# FPGA_1_V1_01.net
KiCad netlist of a schematic drawn in Altium Designer
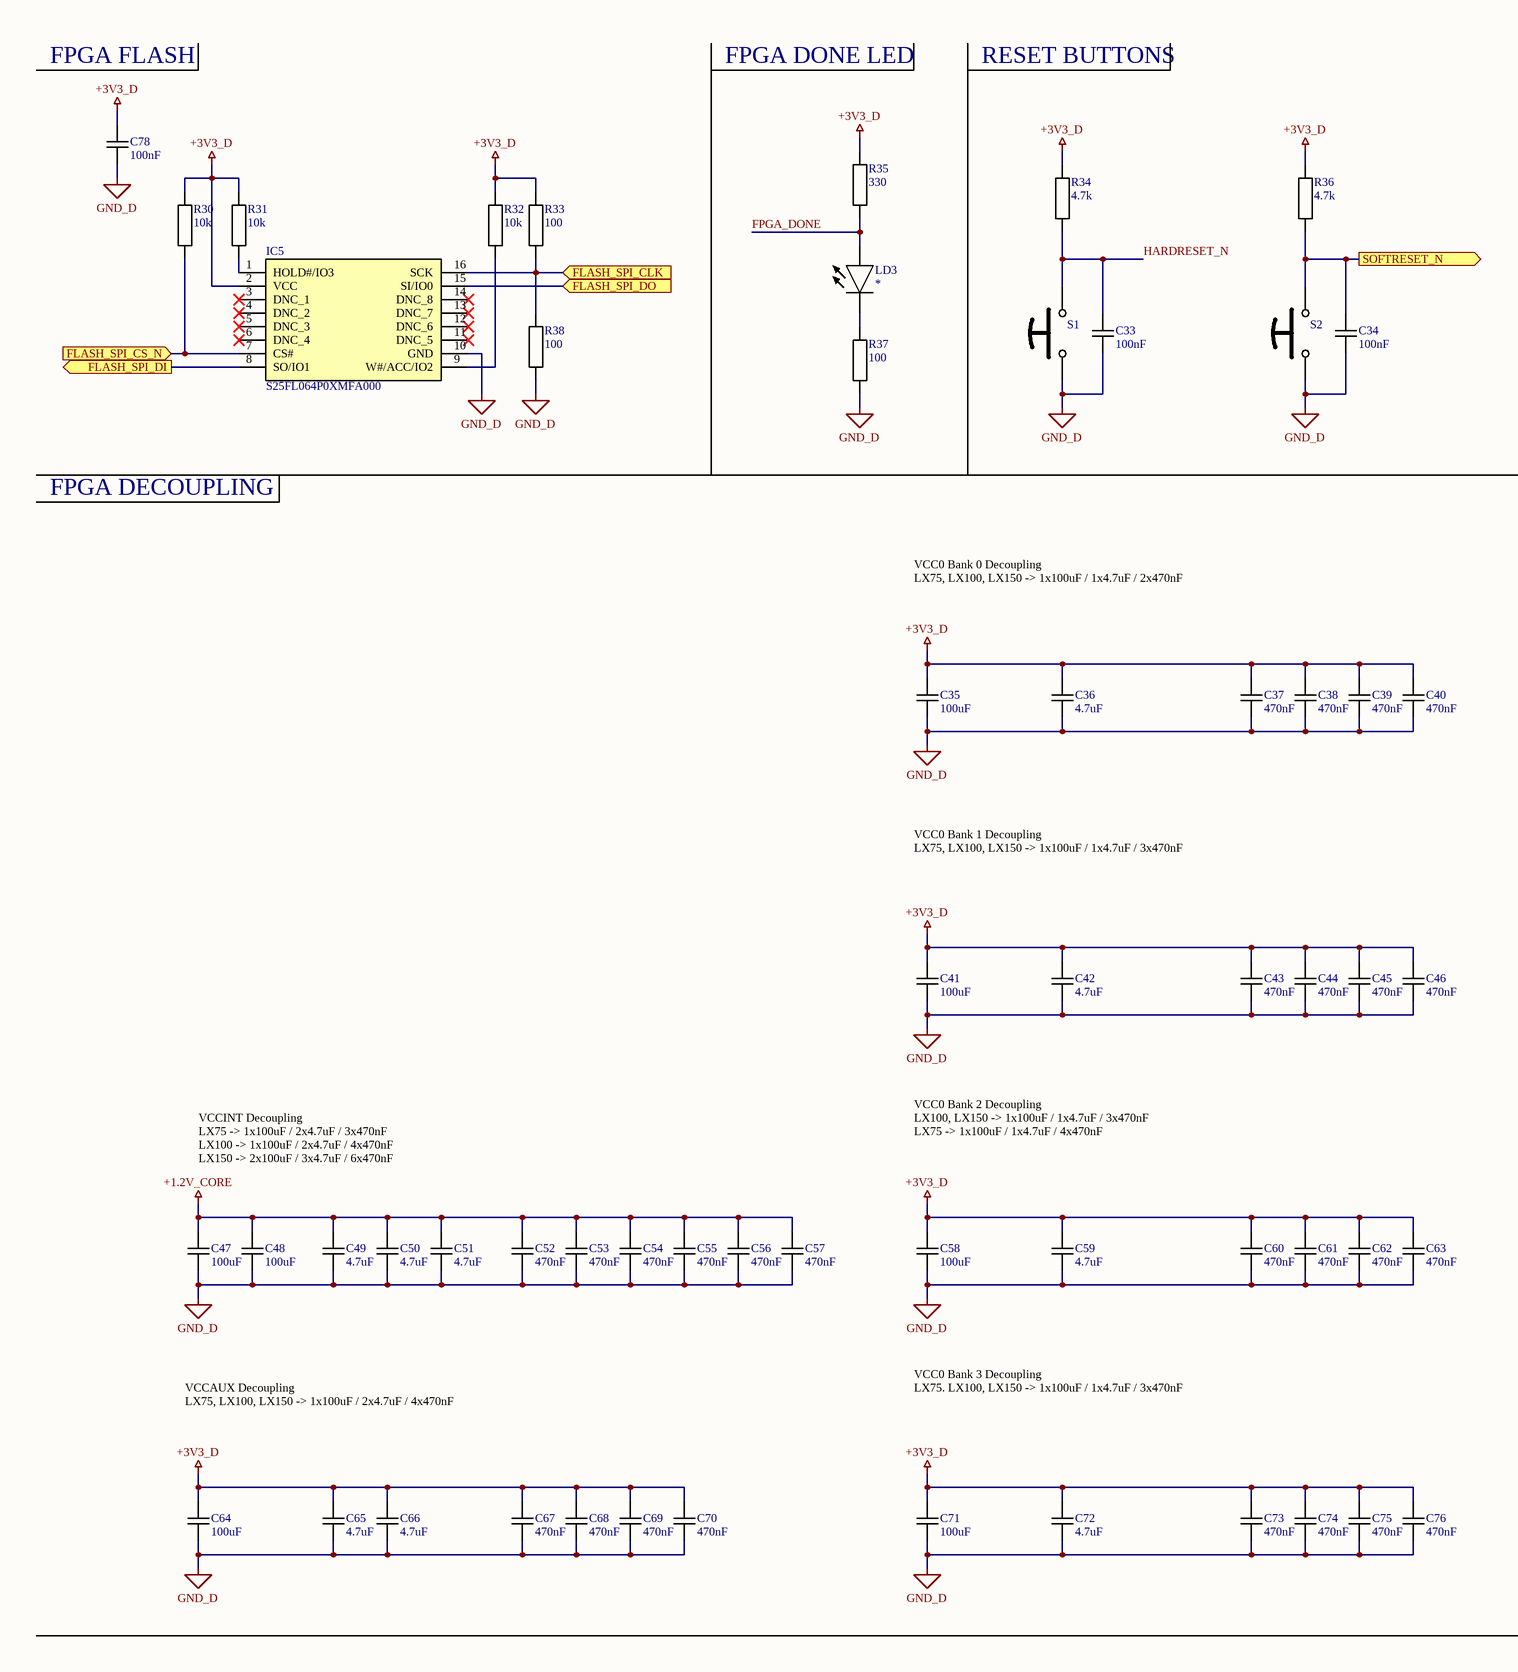
[diagram p0: FPGA_1_V1_01.SchDoc, left]
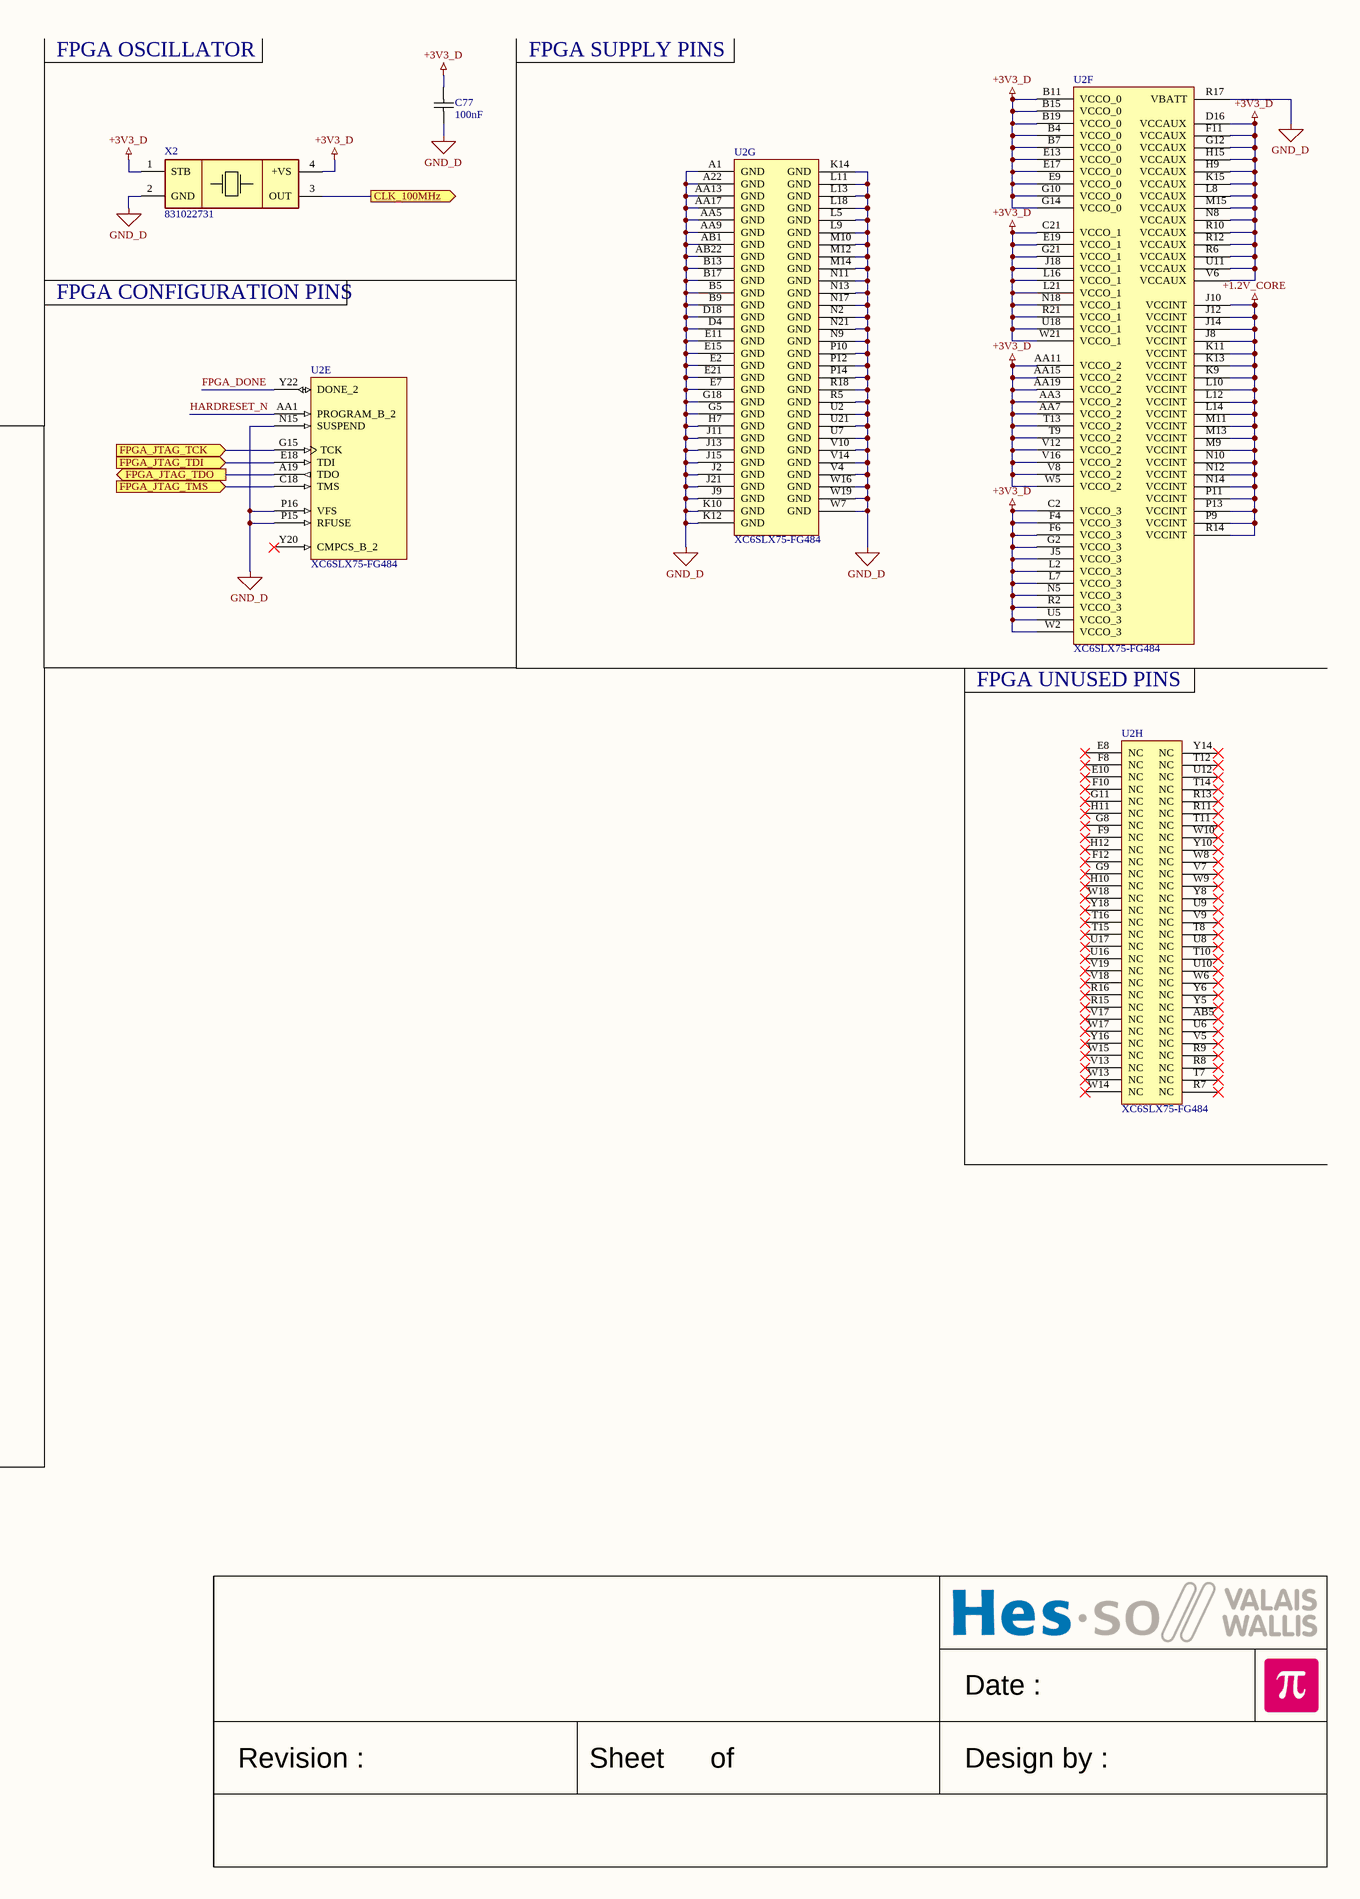
[diagram p1: FPGA_1_V1_01.SchDoc, right]

(export (version "E")
  (design (tool "Eeschema 10.0.6"))
  (components
    (comp (ref "C33")
      (value "100nF")
      (footprint "CAPACITOR 1608 REFLOW")
      (description "Capacitor")
      (libsource (lib "Capacitor") (part "Capacitor"))
    )
    (comp (ref "C34")
      (value "100nF")
      (footprint "CAPACITOR 1608 REFLOW")
      (description "Capacitor")
      (libsource (lib "Capacitor") (part "Capacitor"))
    )
    (comp (ref "C35")
      (value "100uF")
      (footprint "CAPACITOR 3216 REFLOW")
      (description "Capacitor")
      (libsource (lib "Capacitor") (part "Capacitor"))
    )
    (comp (ref "C36")
      (value "4.7uF")
      (footprint "CAPACITOR 1608 REFLOW")
      (description "Capacitor")
      (libsource (lib "Capacitor") (part "Capacitor"))
    )
    (comp (ref "C37")
      (value "470nF")
      (footprint "CAPACITOR 1005 REFLOW")
      (description "Capacitor")
      (libsource (lib "Capacitor") (part "Capacitor"))
    )
    (comp (ref "C38")
      (value "470nF")
      (footprint "CAPACITOR 1005 REFLOW")
      (description "Capacitor")
      (libsource (lib "Capacitor") (part "Capacitor"))
    )
    (comp (ref "C39")
      (value "470nF")
      (footprint "CAPACITOR 1005 REFLOW")
      (description "Capacitor")
      (libsource (lib "Capacitor") (part "Capacitor"))
    )
    (comp (ref "C40")
      (value "470nF")
      (footprint "CAPACITOR 1005 REFLOW")
      (description "Capacitor")
      (libsource (lib "Capacitor") (part "Capacitor"))
    )
    (comp (ref "C41")
      (value "100uF")
      (footprint "CAPACITOR 3216 REFLOW")
      (description "Capacitor")
      (libsource (lib "Capacitor") (part "Capacitor"))
    )
    (comp (ref "C42")
      (value "4.7uF")
      (footprint "CAPACITOR 1608 REFLOW")
      (description "Capacitor")
      (libsource (lib "Capacitor") (part "Capacitor"))
    )
    (comp (ref "C43")
      (value "470nF")
      (footprint "CAPACITOR 1005 REFLOW")
      (description "Capacitor")
      (libsource (lib "Capacitor") (part "Capacitor"))
    )
    (comp (ref "C44")
      (value "470nF")
      (footprint "CAPACITOR 1005 REFLOW")
      (description "Capacitor")
      (libsource (lib "Capacitor") (part "Capacitor"))
    )
    (comp (ref "C45")
      (value "470nF")
      (footprint "CAPACITOR 1005 REFLOW")
      (description "Capacitor")
      (libsource (lib "Capacitor") (part "Capacitor"))
    )
    (comp (ref "C46")
      (value "470nF")
      (footprint "CAPACITOR 1005 REFLOW")
      (description "Capacitor")
      (libsource (lib "Capacitor") (part "Capacitor"))
    )
    (comp (ref "C47")
      (value "100uF")
      (footprint "CAPACITOR 3216 REFLOW")
      (description "Capacitor")
      (libsource (lib "Capacitor") (part "Capacitor"))
    )
    (comp (ref "C48")
      (value "100uF")
      (footprint "CAPACITOR 3216 REFLOW")
      (description "Capacitor")
      (libsource (lib "Capacitor") (part "Capacitor"))
    )
    (comp (ref "C49")
      (value "4.7uF")
      (footprint "CAPACITOR 1608 REFLOW")
      (description "Capacitor")
      (libsource (lib "Capacitor") (part "Capacitor"))
    )
    (comp (ref "C50")
      (value "4.7uF")
      (footprint "CAPACITOR 1608 REFLOW")
      (description "Capacitor")
      (libsource (lib "Capacitor") (part "Capacitor"))
    )
    (comp (ref "C51")
      (value "4.7uF")
      (footprint "CAPACITOR 1608 REFLOW")
      (description "Capacitor")
      (libsource (lib "Capacitor") (part "Capacitor"))
    )
    (comp (ref "C52")
      (value "470nF")
      (footprint "CAPACITOR 1005 REFLOW")
      (description "Capacitor")
      (libsource (lib "Capacitor") (part "Capacitor"))
    )
    (comp (ref "C53")
      (value "470nF")
      (footprint "CAPACITOR 1005 REFLOW")
      (description "Capacitor")
      (libsource (lib "Capacitor") (part "Capacitor"))
    )
    (comp (ref "C54")
      (value "470nF")
      (footprint "CAPACITOR 1005 REFLOW")
      (description "Capacitor")
      (libsource (lib "Capacitor") (part "Capacitor"))
    )
    (comp (ref "C55")
      (value "470nF")
      (footprint "CAPACITOR 1005 REFLOW")
      (description "Capacitor")
      (libsource (lib "Capacitor") (part "Capacitor"))
    )
    (comp (ref "C56")
      (value "470nF")
      (footprint "CAPACITOR 1005 REFLOW")
      (description "Capacitor")
      (libsource (lib "Capacitor") (part "Capacitor"))
    )
    (comp (ref "C57")
      (value "470nF")
      (footprint "CAPACITOR 1005 REFLOW")
      (description "Capacitor")
      (libsource (lib "Capacitor") (part "Capacitor"))
    )
    (comp (ref "C58")
      (value "100uF")
      (footprint "CAPACITOR 3216 REFLOW")
      (description "Capacitor")
      (libsource (lib "Capacitor") (part "Capacitor"))
    )
    (comp (ref "C59")
      (value "4.7uF")
      (footprint "CAPACITOR 1608 REFLOW")
      (description "Capacitor")
      (libsource (lib "Capacitor") (part "Capacitor"))
    )
    (comp (ref "C60")
      (value "470nF")
      (footprint "CAPACITOR 1005 REFLOW")
      (description "Capacitor")
      (libsource (lib "Capacitor") (part "Capacitor"))
    )
    (comp (ref "C61")
      (value "470nF")
      (footprint "CAPACITOR 1005 REFLOW")
      (description "Capacitor")
      (libsource (lib "Capacitor") (part "Capacitor"))
    )
    (comp (ref "C62")
      (value "470nF")
      (footprint "CAPACITOR 1005 REFLOW")
      (description "Capacitor")
      (libsource (lib "Capacitor") (part "Capacitor"))
    )
    (comp (ref "C63")
      (value "470nF")
      (footprint "CAPACITOR 1005 REFLOW")
      (description "Capacitor")
      (libsource (lib "Capacitor") (part "Capacitor"))
    )
    (comp (ref "C64")
      (value "100uF")
      (footprint "CAPACITOR 3216 REFLOW")
      (description "Capacitor")
      (libsource (lib "Capacitor") (part "Capacitor"))
    )
    (comp (ref "C65")
      (value "4.7uF")
      (footprint "CAPACITOR 1608 REFLOW")
      (description "Capacitor")
      (libsource (lib "Capacitor") (part "Capacitor"))
    )
    (comp (ref "C66")
      (value "4.7uF")
      (footprint "CAPACITOR 1608 REFLOW")
      (description "Capacitor")
      (libsource (lib "Capacitor") (part "Capacitor"))
    )
    (comp (ref "C67")
      (value "470nF")
      (footprint "CAPACITOR 1005 REFLOW")
      (description "Capacitor")
      (libsource (lib "Capacitor") (part "Capacitor"))
    )
    (comp (ref "C68")
      (value "470nF")
      (footprint "CAPACITOR 1005 REFLOW")
      (description "Capacitor")
      (libsource (lib "Capacitor") (part "Capacitor"))
    )
    (comp (ref "C69")
      (value "470nF")
      (footprint "CAPACITOR 1005 REFLOW")
      (description "Capacitor")
      (libsource (lib "Capacitor") (part "Capacitor"))
    )
    (comp (ref "C70")
      (value "470nF")
      (footprint "CAPACITOR 1005 REFLOW")
      (description "Capacitor")
      (libsource (lib "Capacitor") (part "Capacitor"))
    )
    (comp (ref "C71")
      (value "100uF")
      (footprint "CAPACITOR 3216 REFLOW")
      (description "Capacitor")
      (libsource (lib "Capacitor") (part "Capacitor"))
    )
    (comp (ref "C72")
      (value "4.7uF")
      (footprint "CAPACITOR 1608 REFLOW")
      (description "Capacitor")
      (libsource (lib "Capacitor") (part "Capacitor"))
    )
    (comp (ref "C73")
      (value "470nF")
      (footprint "CAPACITOR 1005 REFLOW")
      (description "Capacitor")
      (libsource (lib "Capacitor") (part "Capacitor"))
    )
    (comp (ref "C74")
      (value "470nF")
      (footprint "CAPACITOR 1005 REFLOW")
      (description "Capacitor")
      (libsource (lib "Capacitor") (part "Capacitor"))
    )
    (comp (ref "C75")
      (value "470nF")
      (footprint "CAPACITOR 1005 REFLOW")
      (description "Capacitor")
      (libsource (lib "Capacitor") (part "Capacitor"))
    )
    (comp (ref "C76")
      (value "470nF")
      (footprint "CAPACITOR 1005 REFLOW")
      (description "Capacitor")
      (libsource (lib "Capacitor") (part "Capacitor"))
    )
    (comp (ref "C77")
      (value "100nF")
      (footprint "CAPACITOR 1608 REFLOW")
      (description "Capacitor")
      (libsource (lib "Capacitor") (part "Capacitor"))
    )
    (comp (ref "C78")
      (value "100nF")
      (footprint "CAPACITOR 1608 REFLOW")
      (description "Capacitor")
      (libsource (lib "Capacitor") (part "Capacitor"))
    )
    (comp (ref "IC5")
      (value "S25FL064P0XMFA000")
      (footprint "SamacSys:SOIC127P1030X265-16N")
      (description "Integrated Circuit")
      (fields (field (name "MOUSER PART NUMBER") "727-S25FL064P0XMFA00"))
      (libsource (lib "SamacSys") (part "S25FL064P0XMFA000"))
    )
    (comp (ref "LD3")
      (value "*")
      (footprint "LED 1608 REFLOW")
      (description "LED generic")
      (libsource (lib "Diode") (part "LED"))
    )
    (comp (ref "R30")
      (value "10k")
      (footprint "RESISTOR 1608 REFLOW")
      (description "Resistor 1% 50V 100mW 1608(0603)")
      (libsource (lib "Resistor") (part "Resistor"))
    )
    (comp (ref "R31")
      (value "10k")
      (footprint "RESISTOR 1608 REFLOW")
      (description "Resistor 1% 50V 100mW 1608(0603)")
      (libsource (lib "Resistor") (part "Resistor"))
    )
    (comp (ref "R32")
      (value "10k")
      (footprint "RESISTOR 1608 REFLOW")
      (description "Resistor 1% 50V 100mW 1608(0603)")
      (libsource (lib "Resistor") (part "Resistor"))
    )
    (comp (ref "R33")
      (value "100")
      (footprint "RESISTOR 1608 REFLOW")
      (description "Resistor 1% 50V 100mW 1608(0603)")
      (libsource (lib "Resistor") (part "Resistor"))
    )
    (comp (ref "R34")
      (value "4.7k")
      (footprint "RESISTOR 1608 REFLOW")
      (description "Resistor 1% 50V 125mW 2012(0805)")
      (libsource (lib "Resistor") (part "Resistor"))
    )
    (comp (ref "R35")
      (value "330")
      (footprint "RESISTOR 1608 REFLOW")
      (description "Resistor 1% 50V 125mW 2012(0805)")
      (libsource (lib "Resistor") (part "Resistor"))
    )
    (comp (ref "R36")
      (value "4.7k")
      (footprint "RESISTOR 1608 REFLOW")
      (description "Resistor 1% 50V 125mW 2012(0805)")
      (libsource (lib "Resistor") (part "Resistor"))
    )
    (comp (ref "R37")
      (value "100")
      (footprint "RESISTOR 1608 REFLOW")
      (description "Resistor 1% 50V 125mW 2012(0805)")
      (libsource (lib "Resistor") (part "Resistor"))
    )
    (comp (ref "R38")
      (value "100")
      (footprint "RESISTOR 1608 REFLOW")
      (description "Resistor 1% 50V 100mW 1608(0603)")
      (libsource (lib "Resistor") (part "Resistor"))
    )
    (comp (ref "S1")
      (value "*")
      (footprint "Push Button C6.0x3.5 Tyco FSMSM")
      (description "Push Button, 2 pins")
      (libsource (lib "Button") (part "Push Button 2Pins"))
    )
    (comp (ref "S2")
      (value "*")
      (footprint "Push Button C6.0x3.5 Tyco FSMSM")
      (description "Push Button, 2 pins")
      (libsource (lib "Button") (part "Push Button 2Pins"))
    )
    (comp (ref "U2")
      (value "XC6SLX75-FG484")
      (footprint "BGA484 P1.0 C23X23 H2.2")
      (description "Spartan-6 LXT 1.2V FPGA, 268 User I/Os, 484-Ball Fine-Pitch BGA (1.0mm Pitch)")
      (libsource (lib "Processor") (part "XC6SLX75-FG484"))
    )
    (comp (ref "X2")
      (value "831022731")
      (footprint "Oscillator C5.2x7.2 IQD LFSPXO")
      (description "Oscillator C5.2x7.2 IQD LFSPXO")
      (libsource (lib "Oscillator") (part "Oscillator C5.2x7.2 IQD LFSPXO"))
    )
  )
  (nets
    (net (code "1") (name "+1.2V_CORE") (class "Default")
      (node (ref "C47") (pin "1") (pinfunction "1_1") (pintype "passive"))
      (node (ref "C48") (pin "1") (pinfunction "1_1") (pintype "passive"))
      (node (ref "C49") (pin "1") (pinfunction "1_1") (pintype "passive"))
      (node (ref "C50") (pin "1") (pinfunction "1_1") (pintype "passive"))
      (node (ref "C51") (pin "1") (pinfunction "1_1") (pintype "passive"))
      (node (ref "C52") (pin "1") (pinfunction "1_1") (pintype "passive"))
      (node (ref "C53") (pin "1") (pinfunction "1_1") (pintype "passive"))
      (node (ref "C54") (pin "1") (pinfunction "1_1") (pintype "passive"))
      (node (ref "C55") (pin "1") (pinfunction "1_1") (pintype "passive"))
      (node (ref "C56") (pin "1") (pinfunction "1_1") (pintype "passive"))
      (node (ref "C57") (pin "1") (pinfunction "1_1") (pintype "passive"))
      (node (ref "U2") (pin "J10") (pinfunction "VCCINT_J10") (pintype "power_in"))
      (node (ref "U2") (pin "J12") (pinfunction "VCCINT_J12") (pintype "power_in"))
      (node (ref "U2") (pin "J14") (pinfunction "VCCINT_J14") (pintype "power_in"))
      (node (ref "U2") (pin "J8") (pinfunction "VCCINT_J8") (pintype "power_in"))
      (node (ref "U2") (pin "K11") (pinfunction "VCCINT_K11") (pintype "power_in"))
      (node (ref "U2") (pin "K13") (pinfunction "VCCINT_K13") (pintype "power_in"))
      (node (ref "U2") (pin "K9") (pinfunction "VCCINT_K9") (pintype "power_in"))
      (node (ref "U2") (pin "L10") (pinfunction "VCCINT_L10") (pintype "power_in"))
      (node (ref "U2") (pin "L12") (pinfunction "VCCINT_L12") (pintype "power_in"))
      (node (ref "U2") (pin "L14") (pinfunction "VCCINT_L14") (pintype "power_in"))
      (node (ref "U2") (pin "M11") (pinfunction "VCCINT_M11") (pintype "power_in"))
      (node (ref "U2") (pin "M13") (pinfunction "VCCINT_M13") (pintype "power_in"))
      (node (ref "U2") (pin "M9") (pinfunction "VCCINT_M9") (pintype "power_in"))
      (node (ref "U2") (pin "N10") (pinfunction "VCCINT_N10") (pintype "power_in"))
      (node (ref "U2") (pin "N12") (pinfunction "VCCINT_N12") (pintype "power_in"))
      (node (ref "U2") (pin "N14") (pinfunction "VCCINT_N14") (pintype "power_in"))
      (node (ref "U2") (pin "P11") (pinfunction "VCCINT_P11") (pintype "power_in"))
      (node (ref "U2") (pin "P13") (pinfunction "VCCINT_P13") (pintype "power_in"))
      (node (ref "U2") (pin "P9") (pinfunction "VCCINT_P9") (pintype "power_in"))
      (node (ref "U2") (pin "R14") (pinfunction "VCCINT_R14") (pintype "power_in"))
    )
    (net (code "2") (name "+3V3_D") (class "Default")
      (node (ref "C35") (pin "1") (pinfunction "1_1") (pintype "passive"))
      (node (ref "C36") (pin "1") (pinfunction "1_1") (pintype "passive"))
      (node (ref "C37") (pin "1") (pinfunction "1_1") (pintype "passive"))
      (node (ref "C38") (pin "1") (pinfunction "1_1") (pintype "passive"))
      (node (ref "C39") (pin "1") (pinfunction "1_1") (pintype "passive"))
      (node (ref "C40") (pin "1") (pinfunction "1_1") (pintype "passive"))
      (node (ref "C41") (pin "1") (pinfunction "1_1") (pintype "passive"))
      (node (ref "C42") (pin "1") (pinfunction "1_1") (pintype "passive"))
      (node (ref "C43") (pin "1") (pinfunction "1_1") (pintype "passive"))
      (node (ref "C44") (pin "1") (pinfunction "1_1") (pintype "passive"))
      (node (ref "C45") (pin "1") (pinfunction "1_1") (pintype "passive"))
      (node (ref "C46") (pin "1") (pinfunction "1_1") (pintype "passive"))
      (node (ref "C58") (pin "1") (pinfunction "1_1") (pintype "passive"))
      (node (ref "C59") (pin "1") (pinfunction "1_1") (pintype "passive"))
      (node (ref "C60") (pin "1") (pinfunction "1_1") (pintype "passive"))
      (node (ref "C61") (pin "1") (pinfunction "1_1") (pintype "passive"))
      (node (ref "C62") (pin "1") (pinfunction "1_1") (pintype "passive"))
      (node (ref "C63") (pin "1") (pinfunction "1_1") (pintype "passive"))
      (node (ref "C64") (pin "1") (pinfunction "1_1") (pintype "passive"))
      (node (ref "C65") (pin "1") (pinfunction "1_1") (pintype "passive"))
      (node (ref "C66") (pin "1") (pinfunction "1_1") (pintype "passive"))
      (node (ref "C67") (pin "1") (pinfunction "1_1") (pintype "passive"))
      (node (ref "C68") (pin "1") (pinfunction "1_1") (pintype "passive"))
      (node (ref "C69") (pin "1") (pinfunction "1_1") (pintype "passive"))
      (node (ref "C70") (pin "1") (pinfunction "1_1") (pintype "passive"))
      (node (ref "C71") (pin "1") (pinfunction "1_1") (pintype "passive"))
      (node (ref "C72") (pin "1") (pinfunction "1_1") (pintype "passive"))
      (node (ref "C73") (pin "1") (pinfunction "1_1") (pintype "passive"))
      (node (ref "C74") (pin "1") (pinfunction "1_1") (pintype "passive"))
      (node (ref "C75") (pin "1") (pinfunction "1_1") (pintype "passive"))
      (node (ref "C76") (pin "1") (pinfunction "1_1") (pintype "passive"))
      (node (ref "C77") (pin "2") (pinfunction "2_2") (pintype "passive"))
      (node (ref "C78") (pin "2") (pinfunction "2_2") (pintype "passive"))
      (node (ref "IC5") (pin "2") (pinfunction "VCC_2") (pintype "passive"))
      (node (ref "R30") (pin "2") (pinfunction "2_2") (pintype "passive"))
      (node (ref "R31") (pin "2") (pinfunction "2_2") (pintype "passive"))
      (node (ref "R32") (pin "2") (pinfunction "2_2") (pintype "passive"))
      (node (ref "R33") (pin "2") (pinfunction "2_2") (pintype "passive"))
      (node (ref "R34") (pin "2") (pinfunction "2_2") (pintype "passive"))
      (node (ref "R35") (pin "2") (pinfunction "2_2") (pintype "passive"))
      (node (ref "R36") (pin "2") (pinfunction "2_2") (pintype "passive"))
      (node (ref "U2") (pin "AA11") (pinfunction "VCCO_2_AA11") (pintype "power_in"))
      (node (ref "U2") (pin "AA15") (pinfunction "VCCO_2_AA15") (pintype "power_in"))
      (node (ref "U2") (pin "AA19") (pinfunction "VCCO_2_AA19") (pintype "power_in"))
      (node (ref "U2") (pin "AA3") (pinfunction "VCCO_2_AA3") (pintype "power_in"))
      (node (ref "U2") (pin "AA7") (pinfunction "VCCO_2_AA7") (pintype "power_in"))
      (node (ref "U2") (pin "B11") (pinfunction "VCCO_0_B11") (pintype "power_in"))
      (node (ref "U2") (pin "B15") (pinfunction "VCCO_0_B15") (pintype "power_in"))
      (node (ref "U2") (pin "B19") (pinfunction "VCCO_0_B19") (pintype "power_in"))
      (node (ref "U2") (pin "B4") (pinfunction "VCCO_0_B4") (pintype "power_in"))
      (node (ref "U2") (pin "B7") (pinfunction "VCCO_0_B7") (pintype "power_in"))
      (node (ref "U2") (pin "C2") (pinfunction "VCCO_3_C2") (pintype "power_in"))
      (node (ref "U2") (pin "C21") (pinfunction "VCCO_1_C21") (pintype "power_in"))
      (node (ref "U2") (pin "D16") (pinfunction "VCCAUX_D16") (pintype "power_in"))
      (node (ref "U2") (pin "E13") (pinfunction "VCCO_0_E13") (pintype "power_in"))
      (node (ref "U2") (pin "E17") (pinfunction "VCCO_0_E17") (pintype "power_in"))
      (node (ref "U2") (pin "E19") (pinfunction "VCCO_1_E19") (pintype "power_in"))
      (node (ref "U2") (pin "E9") (pinfunction "VCCO_0_E9") (pintype "power_in"))
      (node (ref "U2") (pin "F11") (pinfunction "VCCAUX_F11") (pintype "power_in"))
      (node (ref "U2") (pin "F4") (pinfunction "VCCO_3_F4") (pintype "power_in"))
      (node (ref "U2") (pin "F6") (pinfunction "VCCO_3_F6") (pintype "power_in"))
      (node (ref "U2") (pin "G10") (pinfunction "VCCO_0_G10") (pintype "power_in"))
      (node (ref "U2") (pin "G12") (pinfunction "VCCAUX_G12") (pintype "power_in"))
      (node (ref "U2") (pin "G14") (pinfunction "VCCO_0_G14") (pintype "power_in"))
      (node (ref "U2") (pin "G2") (pinfunction "VCCO_3_G2") (pintype "power_in"))
      (node (ref "U2") (pin "G21") (pinfunction "VCCO_1_G21") (pintype "power_in"))
      (node (ref "U2") (pin "H15") (pinfunction "VCCAUX_H15") (pintype "power_in"))
      (node (ref "U2") (pin "H9") (pinfunction "VCCAUX_H9") (pintype "power_in"))
      (node (ref "U2") (pin "J18") (pinfunction "VCCO_1_J18") (pintype "power_in"))
      (node (ref "U2") (pin "J5") (pinfunction "VCCO_3_J5") (pintype "power_in"))
      (node (ref "U2") (pin "K15") (pinfunction "VCCAUX_K15") (pintype "power_in"))
      (node (ref "U2") (pin "L16") (pinfunction "VCCO_1_L16") (pintype "power_in"))
      (node (ref "U2") (pin "L2") (pinfunction "VCCO_3_L2") (pintype "power_in"))
      (node (ref "U2") (pin "L21") (pinfunction "VCCO_1_L21") (pintype "power_in"))
      (node (ref "U2") (pin "L7") (pinfunction "VCCO_3_L7") (pintype "power_in"))
      (node (ref "U2") (pin "L8") (pinfunction "VCCAUX_L8") (pintype "power_in"))
      (node (ref "U2") (pin "M15") (pinfunction "VCCAUX_M15") (pintype "power_in"))
      (node (ref "U2") (pin "N18") (pinfunction "VCCO_1_N18") (pintype "power_in"))
      (node (ref "U2") (pin "N5") (pinfunction "VCCO_3_N5") (pintype "power_in"))
      (node (ref "U2") (pin "N8") (pinfunction "VCCAUX_N8") (pintype "power_in"))
      (node (ref "U2") (pin "R10") (pinfunction "VCCAUX_R10") (pintype "power_in"))
      (node (ref "U2") (pin "R12") (pinfunction "VCCAUX_R12") (pintype "power_in"))
      (node (ref "U2") (pin "R2") (pinfunction "VCCO_3_R2") (pintype "power_in"))
      (node (ref "U2") (pin "R21") (pinfunction "VCCO_1_R21") (pintype "power_in"))
      (node (ref "U2") (pin "R6") (pinfunction "VCCAUX_R6") (pintype "power_in"))
      (node (ref "U2") (pin "T13") (pinfunction "VCCO_2_T13") (pintype "power_in"))
      (node (ref "U2") (pin "T9") (pinfunction "VCCO_2_T9") (pintype "power_in"))
      (node (ref "U2") (pin "U11") (pinfunction "VCCAUX_U11") (pintype "power_in"))
      (node (ref "U2") (pin "U18") (pinfunction "VCCO_1_U18") (pintype "power_in"))
      (node (ref "U2") (pin "U5") (pinfunction "VCCO_3_U5") (pintype "power_in"))
      (node (ref "U2") (pin "V12") (pinfunction "VCCO_2_V12") (pintype "power_in"))
      (node (ref "U2") (pin "V16") (pinfunction "VCCO_2_V16") (pintype "power_in"))
      (node (ref "U2") (pin "V6") (pinfunction "VCCAUX_V6") (pintype "power_in"))
      (node (ref "U2") (pin "V8") (pinfunction "VCCO_2_V8") (pintype "power_in"))
      (node (ref "U2") (pin "W2") (pinfunction "VCCO_3_W2") (pintype "power_in"))
      (node (ref "U2") (pin "W21") (pinfunction "VCCO_1_W21") (pintype "power_in"))
      (node (ref "U2") (pin "W5") (pinfunction "VCCO_2_W5") (pintype "power_in"))
      (node (ref "X2") (pin "1") (pinfunction "STB_1") (pintype "passive"))
      (node (ref "X2") (pin "4") (pinfunction "+VS_4") (pintype "passive"))
    )
    (net (code "3") (name "/CLK_100MHz") (class "Default")
      (node (ref "X2") (pin "3") (pinfunction "OUT_3") (pintype "passive"))
    )
    (net (code "4") (name "/FLASH_SPI_CLK") (class "Default")
      (node (ref "IC5") (pin "16") (pinfunction "SCK_16") (pintype "passive"))
      (node (ref "R33") (pin "1") (pinfunction "1_1") (pintype "passive"))
      (node (ref "R38") (pin "2") (pinfunction "2_2") (pintype "passive"))
    )
    (net (code "5") (name "/FLASH_SPI_CS_N") (class "Default")
      (node (ref "IC5") (pin "7") (pinfunction "CS#_7") (pintype "passive"))
      (node (ref "R30") (pin "1") (pinfunction "1_1") (pintype "passive"))
    )
    (net (code "6") (name "/FLASH_SPI_DI") (class "Default")
      (node (ref "IC5") (pin "8") (pinfunction "SO/IO1_8") (pintype "passive"))
    )
    (net (code "7") (name "/FLASH_SPI_DO") (class "Default")
      (node (ref "IC5") (pin "15") (pinfunction "SI/IO0_15") (pintype "passive"))
    )
    (net (code "8") (name "/FPGA_DONE") (class "Default")
      (node (ref "LD3") (pin "2") (pinfunction "A_2") (pintype "passive"))
      (node (ref "R35") (pin "1") (pinfunction "1_1") (pintype "passive"))
      (node (ref "U2") (pin "Y22") (pinfunction "DONE_2_Y22") (pintype "bidirectional"))
    )
    (net (code "9") (name "/FPGA_JTAG_TCK") (class "Default")
      (node (ref "U2") (pin "G15") (pinfunction "TCK_G15") (pintype "input"))
    )
    (net (code "10") (name "/FPGA_JTAG_TDI") (class "Default")
      (node (ref "U2") (pin "E18") (pinfunction "TDI_E18") (pintype "input"))
    )
    (net (code "11") (name "/FPGA_JTAG_TDO") (class "Default")
      (node (ref "U2") (pin "A19") (pinfunction "TDO_A19") (pintype "output"))
    )
    (net (code "12") (name "/FPGA_JTAG_TMS") (class "Default")
      (node (ref "U2") (pin "C18") (pinfunction "TMS_C18") (pintype "input"))
    )
    (net (code "13") (name "/HARDRESET_N") (class "Default")
      (node (ref "C33") (pin "2") (pinfunction "2_2") (pintype "passive"))
      (node (ref "R34") (pin "1") (pinfunction "1_1") (pintype "passive"))
      (node (ref "S1") (pin "2") (pinfunction "2_2") (pintype "passive"))
      (node (ref "U2") (pin "AA1") (pinfunction "PROGRAM_B_2_AA1") (pintype "input"))
    )
    (net (code "14") (name "/SOFTRESET_N") (class "Default")
      (node (ref "C34") (pin "2") (pinfunction "2_2") (pintype "passive"))
      (node (ref "R36") (pin "1") (pinfunction "1_1") (pintype "passive"))
      (node (ref "S2") (pin "2") (pinfunction "2_2") (pintype "passive"))
    )
    (net (code "15") (name "GND_D") (class "Default")
      (node (ref "C33") (pin "1") (pinfunction "1_1") (pintype "passive"))
      (node (ref "C34") (pin "1") (pinfunction "1_1") (pintype "passive"))
      (node (ref "C35") (pin "2") (pinfunction "2_2") (pintype "passive"))
      (node (ref "C36") (pin "2") (pinfunction "2_2") (pintype "passive"))
      (node (ref "C37") (pin "2") (pinfunction "2_2") (pintype "passive"))
      (node (ref "C38") (pin "2") (pinfunction "2_2") (pintype "passive"))
      (node (ref "C39") (pin "2") (pinfunction "2_2") (pintype "passive"))
      (node (ref "C40") (pin "2") (pinfunction "2_2") (pintype "passive"))
      (node (ref "C41") (pin "2") (pinfunction "2_2") (pintype "passive"))
      (node (ref "C42") (pin "2") (pinfunction "2_2") (pintype "passive"))
      (node (ref "C43") (pin "2") (pinfunction "2_2") (pintype "passive"))
      (node (ref "C44") (pin "2") (pinfunction "2_2") (pintype "passive"))
      (node (ref "C45") (pin "2") (pinfunction "2_2") (pintype "passive"))
      (node (ref "C46") (pin "2") (pinfunction "2_2") (pintype "passive"))
      (node (ref "C47") (pin "2") (pinfunction "2_2") (pintype "passive"))
      (node (ref "C48") (pin "2") (pinfunction "2_2") (pintype "passive"))
      (node (ref "C49") (pin "2") (pinfunction "2_2") (pintype "passive"))
      (node (ref "C50") (pin "2") (pinfunction "2_2") (pintype "passive"))
      (node (ref "C51") (pin "2") (pinfunction "2_2") (pintype "passive"))
      (node (ref "C52") (pin "2") (pinfunction "2_2") (pintype "passive"))
      (node (ref "C53") (pin "2") (pinfunction "2_2") (pintype "passive"))
      (node (ref "C54") (pin "2") (pinfunction "2_2") (pintype "passive"))
      (node (ref "C55") (pin "2") (pinfunction "2_2") (pintype "passive"))
      (node (ref "C56") (pin "2") (pinfunction "2_2") (pintype "passive"))
      (node (ref "C57") (pin "2") (pinfunction "2_2") (pintype "passive"))
      (node (ref "C58") (pin "2") (pinfunction "2_2") (pintype "passive"))
      (node (ref "C59") (pin "2") (pinfunction "2_2") (pintype "passive"))
      (node (ref "C60") (pin "2") (pinfunction "2_2") (pintype "passive"))
      (node (ref "C61") (pin "2") (pinfunction "2_2") (pintype "passive"))
      (node (ref "C62") (pin "2") (pinfunction "2_2") (pintype "passive"))
      (node (ref "C63") (pin "2") (pinfunction "2_2") (pintype "passive"))
      (node (ref "C64") (pin "2") (pinfunction "2_2") (pintype "passive"))
      (node (ref "C65") (pin "2") (pinfunction "2_2") (pintype "passive"))
      (node (ref "C66") (pin "2") (pinfunction "2_2") (pintype "passive"))
      (node (ref "C67") (pin "2") (pinfunction "2_2") (pintype "passive"))
      (node (ref "C68") (pin "2") (pinfunction "2_2") (pintype "passive"))
      (node (ref "C69") (pin "2") (pinfunction "2_2") (pintype "passive"))
      (node (ref "C70") (pin "2") (pinfunction "2_2") (pintype "passive"))
      (node (ref "C71") (pin "2") (pinfunction "2_2") (pintype "passive"))
      (node (ref "C72") (pin "2") (pinfunction "2_2") (pintype "passive"))
      (node (ref "C73") (pin "2") (pinfunction "2_2") (pintype "passive"))
      (node (ref "C74") (pin "2") (pinfunction "2_2") (pintype "passive"))
      (node (ref "C75") (pin "2") (pinfunction "2_2") (pintype "passive"))
      (node (ref "C76") (pin "2") (pinfunction "2_2") (pintype "passive"))
      (node (ref "C77") (pin "1") (pinfunction "1_1") (pintype "passive"))
      (node (ref "C78") (pin "1") (pinfunction "1_1") (pintype "passive"))
      (node (ref "IC5") (pin "10") (pinfunction "GND_10") (pintype "passive"))
      (node (ref "R37") (pin "1") (pinfunction "1_1") (pintype "passive"))
      (node (ref "R38") (pin "1") (pinfunction "1_1") (pintype "passive"))
      (node (ref "S1") (pin "1") (pinfunction "1_1") (pintype "passive"))
      (node (ref "S2") (pin "1") (pinfunction "1_1") (pintype "passive"))
      (node (ref "U2") (pin "A1") (pinfunction "GND_A1") (pintype "power_in"))
      (node (ref "U2") (pin "A22") (pinfunction "GND_A22") (pintype "power_in"))
      (node (ref "U2") (pin "AA13") (pinfunction "GND_AA13") (pintype "power_in"))
      (node (ref "U2") (pin "AA17") (pinfunction "GND_AA17") (pintype "power_in"))
      (node (ref "U2") (pin "AA5") (pinfunction "GND_AA5") (pintype "power_in"))
      (node (ref "U2") (pin "AA9") (pinfunction "GND_AA9") (pintype "power_in"))
      (node (ref "U2") (pin "AB1") (pinfunction "GND_AB1") (pintype "power_in"))
      (node (ref "U2") (pin "AB22") (pinfunction "GND_AB22") (pintype "power_in"))
      (node (ref "U2") (pin "B13") (pinfunction "GND_B13") (pintype "power_in"))
      (node (ref "U2") (pin "B17") (pinfunction "GND_B17") (pintype "power_in"))
      (node (ref "U2") (pin "B5") (pinfunction "GND_B5") (pintype "power_in"))
      (node (ref "U2") (pin "B9") (pinfunction "GND_B9") (pintype "power_in"))
      (node (ref "U2") (pin "D18") (pinfunction "GND_D18") (pintype "power_in"))
      (node (ref "U2") (pin "D4") (pinfunction "GND_D4") (pintype "power_in"))
      (node (ref "U2") (pin "E11") (pinfunction "GND_E11") (pintype "power_in"))
      (node (ref "U2") (pin "E15") (pinfunction "GND_E15") (pintype "power_in"))
      (node (ref "U2") (pin "E2") (pinfunction "GND_E2") (pintype "power_in"))
      (node (ref "U2") (pin "E21") (pinfunction "GND_E21") (pintype "power_in"))
      (node (ref "U2") (pin "E7") (pinfunction "GND_E7") (pintype "power_in"))
      (node (ref "U2") (pin "G18") (pinfunction "GND_G18") (pintype "power_in"))
      (node (ref "U2") (pin "G5") (pinfunction "GND_G5") (pintype "power_in"))
      (node (ref "U2") (pin "H7") (pinfunction "GND_H7") (pintype "power_in"))
      (node (ref "U2") (pin "J11") (pinfunction "GND_J11") (pintype "power_in"))
      (node (ref "U2") (pin "J13") (pinfunction "GND_J13") (pintype "power_in"))
      (node (ref "U2") (pin "J15") (pinfunction "GND_J15") (pintype "power_in"))
      (node (ref "U2") (pin "J2") (pinfunction "GND_J2") (pintype "power_in"))
      (node (ref "U2") (pin "J21") (pinfunction "GND_J21") (pintype "power_in"))
      (node (ref "U2") (pin "J9") (pinfunction "GND_J9") (pintype "power_in"))
      (node (ref "U2") (pin "K10") (pinfunction "GND_K10") (pintype "power_in"))
      (node (ref "U2") (pin "K12") (pinfunction "GND_K12") (pintype "power_in"))
      (node (ref "U2") (pin "K14") (pinfunction "GND_K14") (pintype "power_in"))
      (node (ref "U2") (pin "L11") (pinfunction "GND_L11") (pintype "power_in"))
      (node (ref "U2") (pin "L13") (pinfunction "GND_L13") (pintype "power_in"))
      (node (ref "U2") (pin "L18") (pinfunction "GND_L18") (pintype "power_in"))
      (node (ref "U2") (pin "L5") (pinfunction "GND_L5") (pintype "power_in"))
      (node (ref "U2") (pin "L9") (pinfunction "GND_L9") (pintype "power_in"))
      (node (ref "U2") (pin "M10") (pinfunction "GND_M10") (pintype "power_in"))
      (node (ref "U2") (pin "M12") (pinfunction "GND_M12") (pintype "power_in"))
      (node (ref "U2") (pin "M14") (pinfunction "GND_M14") (pintype "power_in"))
      (node (ref "U2") (pin "N11") (pinfunction "GND_N11") (pintype "power_in"))
      (node (ref "U2") (pin "N13") (pinfunction "GND_N13") (pintype "power_in"))
      (node (ref "U2") (pin "N15") (pinfunction "SUSPEND_N15") (pintype "input"))
      (node (ref "U2") (pin "N17") (pinfunction "GND_N17") (pintype "power_in"))
      (node (ref "U2") (pin "N2") (pinfunction "GND_N2") (pintype "power_in"))
      (node (ref "U2") (pin "N21") (pinfunction "GND_N21") (pintype "power_in"))
      (node (ref "U2") (pin "N9") (pinfunction "GND_N9") (pintype "power_in"))
      (node (ref "U2") (pin "P10") (pinfunction "GND_P10") (pintype "power_in"))
      (node (ref "U2") (pin "P12") (pinfunction "GND_P12") (pintype "power_in"))
      (node (ref "U2") (pin "P14") (pinfunction "GND_P14") (pintype "power_in"))
      (node (ref "U2") (pin "P15") (pinfunction "RFUSE_P15") (pintype "input"))
      (node (ref "U2") (pin "P16") (pinfunction "VFS_P16") (pintype "input"))
      (node (ref "U2") (pin "R17") (pinfunction "VBATT_R17") (pintype "power_in"))
      (node (ref "U2") (pin "R18") (pinfunction "GND_R18") (pintype "power_in"))
      (node (ref "U2") (pin "R5") (pinfunction "GND_R5") (pintype "power_in"))
      (node (ref "U2") (pin "U2") (pinfunction "GND_U2") (pintype "power_in"))
      (node (ref "U2") (pin "U21") (pinfunction "GND_U21") (pintype "power_in"))
      (node (ref "U2") (pin "U7") (pinfunction "GND_U7") (pintype "power_in"))
      (node (ref "U2") (pin "V10") (pinfunction "GND_V10") (pintype "power_in"))
      (node (ref "U2") (pin "V14") (pinfunction "GND_V14") (pintype "power_in"))
      (node (ref "U2") (pin "V4") (pinfunction "GND_V4") (pintype "power_in"))
      (node (ref "U2") (pin "W16") (pinfunction "GND_W16") (pintype "power_in"))
      (node (ref "U2") (pin "W19") (pinfunction "GND_W19") (pintype "power_in"))
      (node (ref "U2") (pin "W7") (pinfunction "GND_W7") (pintype "power_in"))
      (node (ref "X2") (pin "2") (pinfunction "GND_2") (pintype "passive"))
    )
    (net (code "16") (name "Net-(IC5-HOLD#{slash}IO3)") (class "Default")
      (node (ref "IC5") (pin "1") (pinfunction "HOLD#/IO3_1") (pintype "passive"))
      (node (ref "R31") (pin "1") (pinfunction "1_1") (pintype "passive"))
    )
    (net (code "17") (name "Net-(IC5-W#{slash}ACC{slash}IO2)") (class "Default")
      (node (ref "IC5") (pin "9") (pinfunction "W#/ACC/IO2_9") (pintype "passive"))
      (node (ref "R32") (pin "1") (pinfunction "1_1") (pintype "passive"))
    )
    (net (code "18") (name "Net-(LD3-C)") (class "Default")
      (node (ref "LD3") (pin "1") (pinfunction "C_1") (pintype "passive"))
      (node (ref "R37") (pin "2") (pinfunction "2_2") (pintype "passive"))
    )
    (net (code "19") (name "unconnected-(IC5-DNC_1-Pad3)") (class "Default")
      (node (ref "IC5") (pin "3") (pinfunction "DNC_1_3") (pintype "passive+no_connect"))
    )
    (net (code "20") (name "unconnected-(IC5-DNC_2-Pad4)") (class "Default")
      (node (ref "IC5") (pin "4") (pinfunction "DNC_2_4") (pintype "passive+no_connect"))
    )
    (net (code "21") (name "unconnected-(IC5-DNC_3-Pad5)") (class "Default")
      (node (ref "IC5") (pin "5") (pinfunction "DNC_3_5") (pintype "passive+no_connect"))
    )
    (net (code "22") (name "unconnected-(IC5-DNC_4-Pad6)") (class "Default")
      (node (ref "IC5") (pin "6") (pinfunction "DNC_4_6") (pintype "passive+no_connect"))
    )
    (net (code "23") (name "unconnected-(IC5-DNC_5-Pad11)") (class "Default")
      (node (ref "IC5") (pin "11") (pinfunction "DNC_5_11") (pintype "passive+no_connect"))
    )
    (net (code "24") (name "unconnected-(IC5-DNC_6-Pad12)") (class "Default")
      (node (ref "IC5") (pin "12") (pinfunction "DNC_6_12") (pintype "passive+no_connect"))
    )
    (net (code "25") (name "unconnected-(IC5-DNC_7-Pad13)") (class "Default")
      (node (ref "IC5") (pin "13") (pinfunction "DNC_7_13") (pintype "passive+no_connect"))
    )
    (net (code "26") (name "unconnected-(IC5-DNC_8-Pad14)") (class "Default")
      (node (ref "IC5") (pin "14") (pinfunction "DNC_8_14") (pintype "passive+no_connect"))
    )
    (net (code "27") (name "unconnected-(U2E-CMPCS_B_2-PadY20)") (class "Default")
      (node (ref "U2") (pin "Y20") (pinfunction "CMPCS_B_2_Y20") (pintype "input+no_connect"))
    )
    (net (code "28") (name "unconnected-(U2H-NC-PadAB5)") (class "Default")
      (node (ref "U2") (pin "AB5") (pinfunction "NC_AB5") (pintype "passive+no_connect"))
    )
    (net (code "29") (name "unconnected-(U2H-NC-PadE8)") (class "Default")
      (node (ref "U2") (pin "E8") (pinfunction "NC_E8") (pintype "passive+no_connect"))
    )
    (net (code "30") (name "unconnected-(U2H-NC-PadE10)") (class "Default")
      (node (ref "U2") (pin "E10") (pinfunction "NC_E10") (pintype "passive+no_connect"))
    )
    (net (code "31") (name "unconnected-(U2H-NC-PadF8)") (class "Default")
      (node (ref "U2") (pin "F8") (pinfunction "NC_F8") (pintype "passive+no_connect"))
    )
    (net (code "32") (name "unconnected-(U2H-NC-PadF9)") (class "Default")
      (node (ref "U2") (pin "F9") (pinfunction "NC_F9") (pintype "passive+no_connect"))
    )
    (net (code "33") (name "unconnected-(U2H-NC-PadF10)") (class "Default")
      (node (ref "U2") (pin "F10") (pinfunction "NC_F10") (pintype "passive+no_connect"))
    )
    (net (code "34") (name "unconnected-(U2H-NC-PadF12)") (class "Default")
      (node (ref "U2") (pin "F12") (pinfunction "NC_F12") (pintype "passive+no_connect"))
    )
    (net (code "35") (name "unconnected-(U2H-NC-PadG8)") (class "Default")
      (node (ref "U2") (pin "G8") (pinfunction "NC_G8") (pintype "passive+no_connect"))
    )
    (net (code "36") (name "unconnected-(U2H-NC-PadG9)") (class "Default")
      (node (ref "U2") (pin "G9") (pinfunction "NC_G9") (pintype "passive+no_connect"))
    )
    (net (code "37") (name "unconnected-(U2H-NC-PadG11)") (class "Default")
      (node (ref "U2") (pin "G11") (pinfunction "NC_G11") (pintype "passive+no_connect"))
    )
    (net (code "38") (name "unconnected-(U2H-NC-PadH10)") (class "Default")
      (node (ref "U2") (pin "H10") (pinfunction "NC_H10") (pintype "passive+no_connect"))
    )
    (net (code "39") (name "unconnected-(U2H-NC-PadH11)") (class "Default")
      (node (ref "U2") (pin "H11") (pinfunction "NC_H11") (pintype "passive+no_connect"))
    )
    (net (code "40") (name "unconnected-(U2H-NC-PadH12)") (class "Default")
      (node (ref "U2") (pin "H12") (pinfunction "NC_H12") (pintype "passive+no_connect"))
    )
    (net (code "41") (name "unconnected-(U2H-NC-PadR7)") (class "Default")
      (node (ref "U2") (pin "R7") (pinfunction "NC_R7") (pintype "passive+no_connect"))
    )
    (net (code "42") (name "unconnected-(U2H-NC-PadR8)") (class "Default")
      (node (ref "U2") (pin "R8") (pinfunction "NC_R8") (pintype "passive+no_connect"))
    )
    (net (code "43") (name "unconnected-(U2H-NC-PadR9)") (class "Default")
      (node (ref "U2") (pin "R9") (pinfunction "NC_R9") (pintype "passive+no_connect"))
    )
    (net (code "44") (name "unconnected-(U2H-NC-PadR11)") (class "Default")
      (node (ref "U2") (pin "R11") (pinfunction "NC_R11") (pintype "passive+no_connect"))
    )
    (net (code "45") (name "unconnected-(U2H-NC-PadR13)") (class "Default")
      (node (ref "U2") (pin "R13") (pinfunction "NC_R13") (pintype "passive+no_connect"))
    )
    (net (code "46") (name "unconnected-(U2H-NC-PadR15)") (class "Default")
      (node (ref "U2") (pin "R15") (pinfunction "NC_R15") (pintype "passive+no_connect"))
    )
    (net (code "47") (name "unconnected-(U2H-NC-PadR16)") (class "Default")
      (node (ref "U2") (pin "R16") (pinfunction "NC_R16") (pintype "passive+no_connect"))
    )
    (net (code "48") (name "unconnected-(U2H-NC-PadT7)") (class "Default")
      (node (ref "U2") (pin "T7") (pinfunction "NC_T7") (pintype "passive+no_connect"))
    )
    (net (code "49") (name "unconnected-(U2H-NC-PadT8)") (class "Default")
      (node (ref "U2") (pin "T8") (pinfunction "NC_T8") (pintype "passive+no_connect"))
    )
    (net (code "50") (name "unconnected-(U2H-NC-PadT10)") (class "Default")
      (node (ref "U2") (pin "T10") (pinfunction "NC_T10") (pintype "passive+no_connect"))
    )
    (net (code "51") (name "unconnected-(U2H-NC-PadT11)") (class "Default")
      (node (ref "U2") (pin "T11") (pinfunction "NC_T11") (pintype "passive+no_connect"))
    )
    (net (code "52") (name "unconnected-(U2H-NC-PadT12)") (class "Default")
      (node (ref "U2") (pin "T12") (pinfunction "NC_T12") (pintype "passive+no_connect"))
    )
    (net (code "53") (name "unconnected-(U2H-NC-PadT14)") (class "Default")
      (node (ref "U2") (pin "T14") (pinfunction "NC_T14") (pintype "passive+no_connect"))
    )
    (net (code "54") (name "unconnected-(U2H-NC-PadT15)") (class "Default")
      (node (ref "U2") (pin "T15") (pinfunction "NC_T15") (pintype "passive+no_connect"))
    )
    (net (code "55") (name "unconnected-(U2H-NC-PadT16)") (class "Default")
      (node (ref "U2") (pin "T16") (pinfunction "NC_T16") (pintype "passive+no_connect"))
    )
    (net (code "56") (name "unconnected-(U2H-NC-PadU6)") (class "Default")
      (node (ref "U2") (pin "U6") (pinfunction "NC_U6") (pintype "passive+no_connect"))
    )
    (net (code "57") (name "unconnected-(U2H-NC-PadU8)") (class "Default")
      (node (ref "U2") (pin "U8") (pinfunction "NC_U8") (pintype "passive+no_connect"))
    )
    (net (code "58") (name "unconnected-(U2H-NC-PadU9)") (class "Default")
      (node (ref "U2") (pin "U9") (pinfunction "NC_U9") (pintype "passive+no_connect"))
    )
    (net (code "59") (name "unconnected-(U2H-NC-PadU10)") (class "Default")
      (node (ref "U2") (pin "U10") (pinfunction "NC_U10") (pintype "passive+no_connect"))
    )
    (net (code "60") (name "unconnected-(U2H-NC-PadU12)") (class "Default")
      (node (ref "U2") (pin "U12") (pinfunction "NC_U12") (pintype "passive+no_connect"))
    )
    (net (code "61") (name "unconnected-(U2H-NC-PadU16)") (class "Default")
      (node (ref "U2") (pin "U16") (pinfunction "NC_U16") (pintype "passive+no_connect"))
    )
    (net (code "62") (name "unconnected-(U2H-NC-PadU17)") (class "Default")
      (node (ref "U2") (pin "U17") (pinfunction "NC_U17") (pintype "passive+no_connect"))
    )
    (net (code "63") (name "unconnected-(U2H-NC-PadV5)") (class "Default")
      (node (ref "U2") (pin "V5") (pinfunction "NC_V5") (pintype "passive+no_connect"))
    )
    (net (code "64") (name "unconnected-(U2H-NC-PadV7)") (class "Default")
      (node (ref "U2") (pin "V7") (pinfunction "NC_V7") (pintype "passive+no_connect"))
    )
    (net (code "65") (name "unconnected-(U2H-NC-PadV9)") (class "Default")
      (node (ref "U2") (pin "V9") (pinfunction "NC_V9") (pintype "passive+no_connect"))
    )
    (net (code "66") (name "unconnected-(U2H-NC-PadV13)") (class "Default")
      (node (ref "U2") (pin "V13") (pinfunction "NC_V13") (pintype "passive+no_connect"))
    )
    (net (code "67") (name "unconnected-(U2H-NC-PadV17)") (class "Default")
      (node (ref "U2") (pin "V17") (pinfunction "NC_V17") (pintype "passive+no_connect"))
    )
    (net (code "68") (name "unconnected-(U2H-NC-PadV18)") (class "Default")
      (node (ref "U2") (pin "V18") (pinfunction "NC_V18") (pintype "passive+no_connect"))
    )
    (net (code "69") (name "unconnected-(U2H-NC-PadV19)") (class "Default")
      (node (ref "U2") (pin "V19") (pinfunction "NC_V19") (pintype "passive+no_connect"))
    )
    (net (code "70") (name "unconnected-(U2H-NC-PadW6)") (class "Default")
      (node (ref "U2") (pin "W6") (pinfunction "NC_W6") (pintype "passive+no_connect"))
    )
    (net (code "71") (name "unconnected-(U2H-NC-PadW8)") (class "Default")
      (node (ref "U2") (pin "W8") (pinfunction "NC_W8") (pintype "passive+no_connect"))
    )
    (net (code "72") (name "unconnected-(U2H-NC-PadW9)") (class "Default")
      (node (ref "U2") (pin "W9") (pinfunction "NC_W9") (pintype "passive+no_connect"))
    )
    (net (code "73") (name "unconnected-(U2H-NC-PadW10)") (class "Default")
      (node (ref "U2") (pin "W10") (pinfunction "NC_W10") (pintype "passive+no_connect"))
    )
    (net (code "74") (name "unconnected-(U2H-NC-PadW13)") (class "Default")
      (node (ref "U2") (pin "W13") (pinfunction "NC_W13") (pintype "passive+no_connect"))
    )
    (net (code "75") (name "unconnected-(U2H-NC-PadW14)") (class "Default")
      (node (ref "U2") (pin "W14") (pinfunction "NC_W14") (pintype "passive+no_connect"))
    )
    (net (code "76") (name "unconnected-(U2H-NC-PadW15)") (class "Default")
      (node (ref "U2") (pin "W15") (pinfunction "NC_W15") (pintype "passive+no_connect"))
    )
    (net (code "77") (name "unconnected-(U2H-NC-PadW17)") (class "Default")
      (node (ref "U2") (pin "W17") (pinfunction "NC_W17") (pintype "passive+no_connect"))
    )
    (net (code "78") (name "unconnected-(U2H-NC-PadW18)") (class "Default")
      (node (ref "U2") (pin "W18") (pinfunction "NC_W18") (pintype "passive+no_connect"))
    )
    (net (code "79") (name "unconnected-(U2H-NC-PadY5)") (class "Default")
      (node (ref "U2") (pin "Y5") (pinfunction "NC_Y5") (pintype "passive+no_connect"))
    )
    (net (code "80") (name "unconnected-(U2H-NC-PadY6)") (class "Default")
      (node (ref "U2") (pin "Y6") (pinfunction "NC_Y6") (pintype "passive+no_connect"))
    )
    (net (code "81") (name "unconnected-(U2H-NC-PadY8)") (class "Default")
      (node (ref "U2") (pin "Y8") (pinfunction "NC_Y8") (pintype "passive+no_connect"))
    )
    (net (code "82") (name "unconnected-(U2H-NC-PadY10)") (class "Default")
      (node (ref "U2") (pin "Y10") (pinfunction "NC_Y10") (pintype "passive+no_connect"))
    )
    (net (code "83") (name "unconnected-(U2H-NC-PadY14)") (class "Default")
      (node (ref "U2") (pin "Y14") (pinfunction "NC_Y14") (pintype "passive+no_connect"))
    )
    (net (code "84") (name "unconnected-(U2H-NC-PadY16)") (class "Default")
      (node (ref "U2") (pin "Y16") (pinfunction "NC_Y16") (pintype "passive+no_connect"))
    )
    (net (code "85") (name "unconnected-(U2H-NC-PadY18)") (class "Default")
      (node (ref "U2") (pin "Y18") (pinfunction "NC_Y18") (pintype "passive+no_connect"))
    )
  )
)
